# ST_LINK_V2-1.net
KiCad netlist of a schematic drawn in Altium Designer
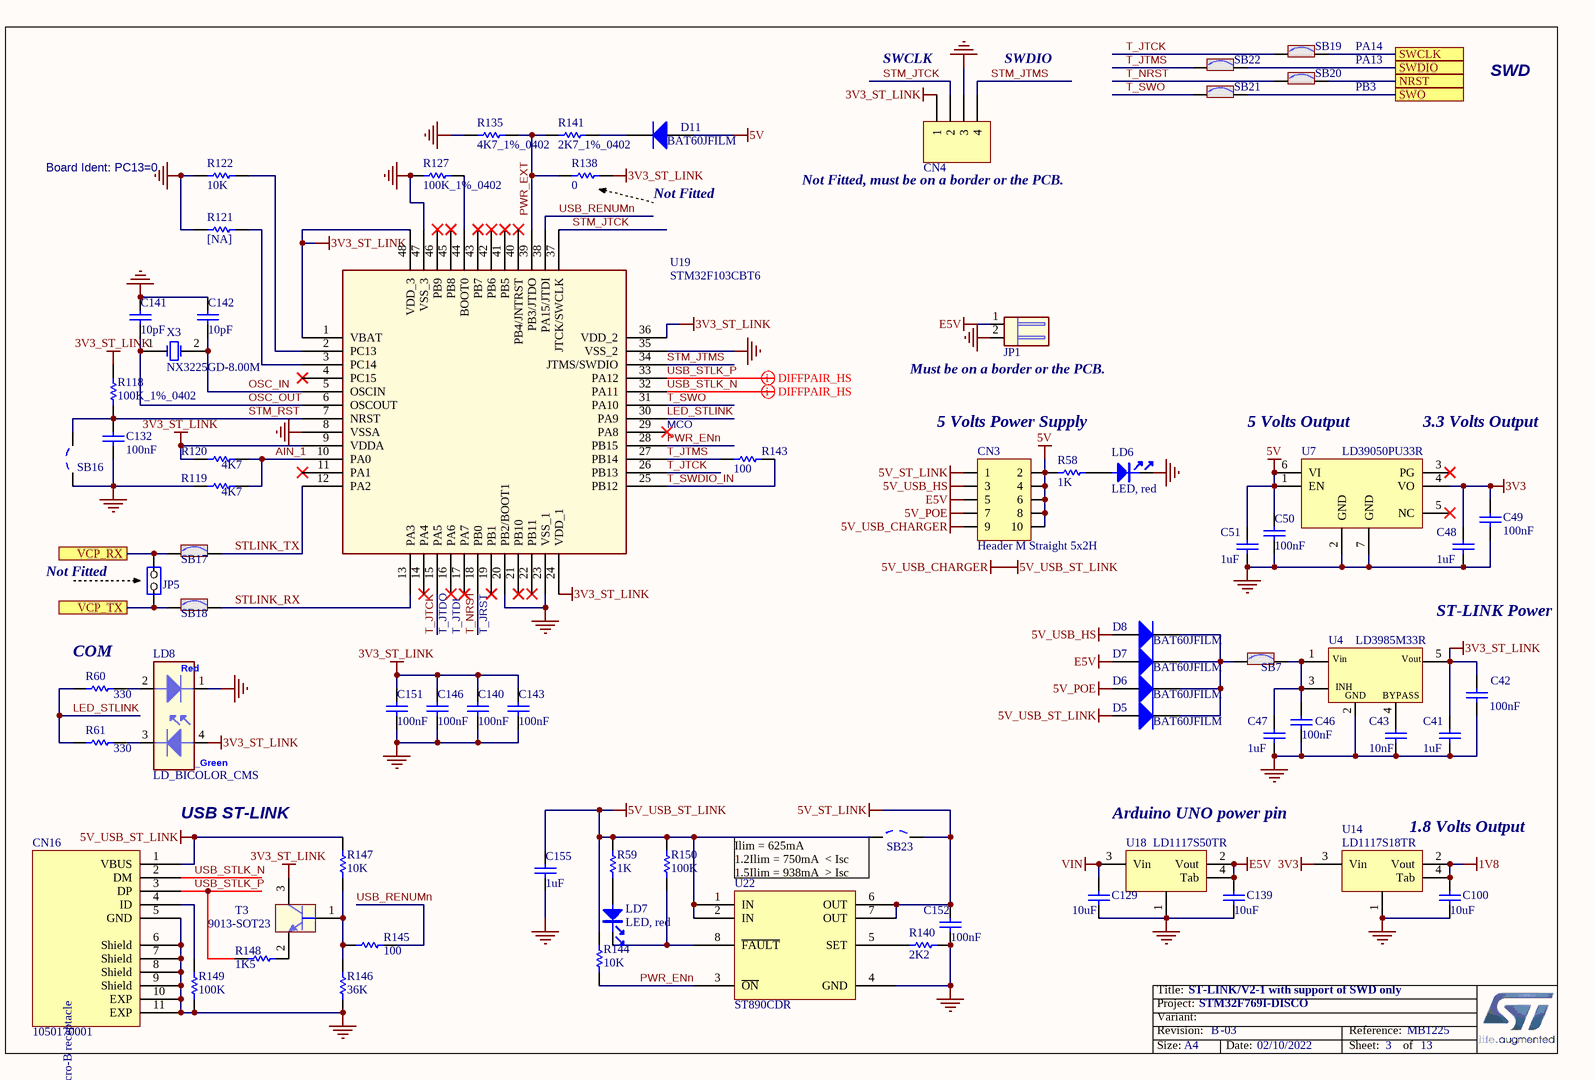
[diagram p0: ST_LINK_V2-1.SCHDOC]

(export (version "E")
  (design (tool "Eeschema 10.0.6"))
  (components
    (comp (ref "C41")
      (value "1uF")
      (footprint "0603C")
      (description "Capacitor,1uF,16V,X5R,10%,0603,YAGEO")
      (libsource (lib "MCD_TOOLS") (part "Cap_1uF_X5R_10%_0603"))
    )
    (comp (ref "C42")
      (value "100nF")
      (footprint "0402C")
      (description "Capacitor,100nF,16V,X7R,10%,0402,YAGEO")
      (libsource (lib "MCD_TOOLS") (part "Cap_100nF_X7R_10%_0402"))
    )
    (comp (ref "C43")
      (value "10nF")
      (footprint "0603C")
      (description "Capacitor,10nF,50V,X7R,10%,0603,YAGEO")
      (libsource (lib "MCD_TOOLS") (part "Cap_10nF_X7R_10%_0603"))
    )
    (comp (ref "C46")
      (value "100nF")
      (footprint "0402C")
      (description "Capacitor,100nF,16V,X7R,10%,0402,YAGEO")
      (libsource (lib "MCD_TOOLS") (part "Cap_100nF_X7R_10%_0402"))
    )
    (comp (ref "C47")
      (value "1uF")
      (footprint "0603C")
      (description "Capacitor,1uF,16V,X5R,10%,0603,YAGEO")
      (libsource (lib "MCD_TOOLS") (part "Cap_1uF_X5R_10%_0603"))
    )
    (comp (ref "C48")
      (value "1uF")
      (footprint "0603C")
      (description "Capacitor,1uF,16V,X5R,10%,0603,YAGEO")
      (libsource (lib "MCD_TOOLS") (part "Cap_1uF_X5R_10%_0603"))
    )
    (comp (ref "C49")
      (value "100nF")
      (footprint "0402C")
      (description "Capacitor,100nF,16V,X7R,10%,0402,YAGEO")
      (libsource (lib "MCD_TOOLS") (part "Cap_100nF_X7R_10%_0402"))
    )
    (comp (ref "C50")
      (value "100nF")
      (footprint "0402C")
      (description "Capacitor,100nF,16V,X7R,10%,0402,YAGEO")
      (libsource (lib "MCD_TOOLS") (part "Cap_100nF_X7R_10%_0402"))
    )
    (comp (ref "C51")
      (value "1uF")
      (footprint "0603C")
      (description "Capacitor,1uF,16V,X5R,10%,0603,YAGEO")
      (libsource (lib "MCD_TOOLS") (part "Cap_1uF_X5R_10%_0603"))
    )
    (comp (ref "C100")
      (value "10uF")
      (footprint "0603C")
      (description "Capacitor,10uF,6.3V,X5R,10%,0603,YAGEO")
      (libsource (lib "MCD_TOOLS") (part "Cap_10uF_X5R_10%_0603"))
    )
    (comp (ref "C129")
      (value "10uF")
      (footprint "0805C")
      (description "Capacitor,10uF,25V,X5R,10%,0805,YAGEO")
      (libsource (lib "MCD_TOOLS") (part "Cap_10uF_X5R_10%_0805"))
    )
    (comp (ref "C132")
      (value "100nF")
      (footprint "0402C")
      (description "Capacitor,100nF,16V,X7R,10%,0402,YAGEO")
      (libsource (lib "MCD_TOOLS") (part "Cap_100nF_X7R_10%_0402"))
    )
    (comp (ref "C139")
      (value "10uF")
      (footprint "0805C")
      (description "Capacitor,10uF,25V,X5R,10%,0805,YAGEO")
      (libsource (lib "MCD_TOOLS") (part "Cap_10uF_X5R_10%_0805"))
    )
    (comp (ref "C140")
      (value "100nF")
      (footprint "0402C")
      (description "Capacitor,100nF,16V,X7R,10%,0402,YAGEO")
      (libsource (lib "MCD_TOOLS") (part "Cap_100nF_X7R_10%_0402"))
    )
    (comp (ref "C141")
      (value "10pF")
      (footprint "0402C")
      (description "Capacitor,10pF,50V,NPO,5%,0402,YAGEO")
      (libsource (lib "MCD_TOOLS") (part "Cap_10pF_NPO_5%_0402"))
    )
    (comp (ref "C142")
      (value "10pF")
      (footprint "0402C")
      (description "Capacitor,10pF,50V,NPO,5%,0402,YAGEO")
      (libsource (lib "MCD_TOOLS") (part "Cap_10pF_NPO_5%_0402"))
    )
    (comp (ref "C143")
      (value "100nF")
      (footprint "0402C")
      (description "Capacitor,100nF,16V,X7R,10%,0402,YAGEO")
      (libsource (lib "MCD_TOOLS") (part "Cap_100nF_X7R_10%_0402"))
    )
    (comp (ref "C146")
      (value "100nF")
      (footprint "0402C")
      (description "Capacitor,100nF,16V,X7R,10%,0402,YAGEO")
      (libsource (lib "MCD_TOOLS") (part "Cap_100nF_X7R_10%_0402"))
    )
    (comp (ref "C151")
      (value "100nF")
      (footprint "0402C")
      (description "Capacitor,100nF,16V,X7R,10%,0402,YAGEO")
      (libsource (lib "MCD_TOOLS") (part "Cap_100nF_X7R_10%_0402"))
    )
    (comp (ref "C152")
      (value "100nF")
      (footprint "0402C")
      (description "Capacitor,100nF,16V,X7R,10%,0402,YAGEO")
      (libsource (lib "MCD_TOOLS") (part "Cap_100nF_X7R_10%_0402"))
    )
    (comp (ref "C155")
      (value "1uF")
      (footprint "0603C")
      (description "Capacitor,1uF,16V,X5R,10%,0603,YAGEO")
      (libsource (lib "MCD_TOOLS_CAPACITOR") (part "Cap_1uF_X5R_10%_0603"))
    )
    (comp (ref "CN3")
      (value "Header M Straight 5x2H")
      (footprint "HDR_2X5_2R54")
      (description "Header Male, 5-Pin, Dual row, Straight, AMD")
      (libsource (lib "MCD_TOOLS_CONNECTOR") (part "Header 5X2M"))
    )
    (comp (ref "CN4")
      (value "Header 4")
      (footprint "HDR_1X4_2R54")
      (description "Header, 4-Pin")
      (fields (field (name "PUBLISHER") "Altium Limited"))
      (libsource (lib "MCD_TOOLS_CONNECTOR") (part "Header 4"))
    )
    (comp (ref "CN16")
      (value "1050170001")
      (footprint "MICRO_USB_B_105017")
      (description "USB-MICRO-B, 1050170001, SMT, MOLEX")
      (libsource (lib "MCD_TOOLS_CONNECTOR") (part "1050170001"))
    )
    (comp (ref "D5")
      (value "BAT60JFILM")
      (footprint "SOD-323")
      (libsource (lib "MCD_TOOLS_MISCELLANEOUS") (part "BAT60JFILM"))
    )
    (comp (ref "D6")
      (value "BAT60JFILM")
      (footprint "SOD-323")
      (libsource (lib "MCD_TOOLS_MISCELLANEOUS") (part "BAT60JFILM"))
    )
    (comp (ref "D7")
      (value "BAT60JFILM")
      (footprint "SOD-323")
      (libsource (lib "MCD_TOOLS_MISCELLANEOUS") (part "BAT60JFILM"))
    )
    (comp (ref "D8")
      (value "BAT60JFILM")
      (footprint "SOD-323")
      (libsource (lib "MCD_TOOLS_MISCELLANEOUS") (part "BAT60JFILM"))
    )
    (comp (ref "D11")
      (value "BAT60JFILM")
      (footprint "SOD-323")
      (libsource (lib "MCD_TOOLS_MISCELLANEOUS") (part "BAT60JFILM"))
    )
    (comp (ref "JP1")
      (value "WF25402-06421")
      (footprint "HDR_1X2_2R54_RA_11R35")
      (description "Header, 2-Pins, Single row, Right Angle, 2.54 mm pitch, DIP")
      (libsource (lib "MCD_TOOLS_CONNECTOR") (part "JP2_RA"))
    )
    (comp (ref "JP5") (value "JP2") (footprint "SIP2") (libsource (lib "MCD_TOOLS_CONNECTOR") (part "JP2")))
    (comp (ref "LD6")
      (value "LED, red")
      (footprint "0603D")
      (description "LED, red, 0603")
      (libsource (lib "MCD_TOOLS") (part "LED_red"))
    )
    (comp (ref "LD7")
      (value "LED, red")
      (footprint "0603D")
      (description "LED, red, 0603")
      (libsource (lib "MCD_TOOLS") (part "LED_red"))
    )
    (comp (ref "LD8")
      (value "LD_BICOLOR_CMS")
      (footprint "LED2_3528")
      (description "Bicolor Led")
      (libsource (lib "MCD_TOOLS_MISCELLANEOUS") (part "LD_BICOLOR_CMS"))
    )
    (comp (ref "R58")
      (value "1K")
      (footprint "0402R")
      (description "Resistor,1K,0402,1%,YAGEO")
      (libsource (lib "MCD_TOOLS") (part "Res_1K_1%_0402"))
    )
    (comp (ref "R59")
      (value "1K")
      (footprint "0402R")
      (description "Resistor,1K,0402,1%,YAGEO")
      (libsource (lib "MCD_TOOLS") (part "Res_1K_1%_0402"))
    )
    (comp (ref "R60")
      (value "330")
      (footprint "0402R")
      (description "Resistor,330,0402,1%,YAGEO")
      (libsource (lib "MCD_TOOLS") (part "Res_330_1%_0402"))
    )
    (comp (ref "R61")
      (value "330")
      (footprint "0402R")
      (description "Resistor,330,0402,1%,YAGEO")
      (libsource (lib "MCD_TOOLS") (part "Res_330_1%_0402"))
    )
    (comp (ref "R118")
      (value "100K_1%_0402")
      (footprint "0402R")
      (description "Resistor,100K,0402,1%,YAGEO")
      (libsource (lib "MCD_TOOLS_RESISTOR") (part "Res_100K_1%_0402"))
    )
    (comp (ref "R119")
      (value "4K7")
      (footprint "0402R")
      (description "Resistor,4K7,0402,1%,YAGEO")
      (libsource (lib "MCD_TOOLS_RESISTOR") (part "Res_4K7_1%_0402"))
    )
    (comp (ref "R120")
      (value "4K7")
      (footprint "0402R")
      (description "Resistor,4K7,0402,1%,YAGEO")
      (libsource (lib "MCD_TOOLS_RESISTOR") (part "Res_4K7_1%_0402"))
    )
    (comp (ref "R121")
      (value "[NA]")
      (footprint "0402R")
      (description "Resistor,[NA],0402")
      (libsource (lib "MCD_TOOLS") (part "Res_NA_0402"))
    )
    (comp (ref "R122")
      (value "10K")
      (footprint "0402R")
      (description "Resistor,10K,0402,1%,YAGEO")
      (libsource (lib "MCD_TOOLS") (part "Res_10K_1%_0402"))
    )
    (comp (ref "R127")
      (value "100K_1%_0402")
      (footprint "0402R")
      (description "Resistor,100K,0402,1%,YAGEO")
      (libsource (lib "MCD_TOOLS_RESISTOR") (part "Res_100K_1%_0402"))
    )
    (comp (ref "R135")
      (value "4K7_1%_0402")
      (footprint "0402R")
      (description "Resistor,4K7,0402,1%,YAGEO")
      (libsource (lib "MCD_TOOLS_RESISTOR") (part "Res_4K7_1%_0402"))
    )
    (comp (ref "R138")
      (value "0")
      (footprint "0402R")
      (description "Resistor,0,0402,5%,YAGEO")
      (libsource (lib "MCD_TOOLS") (part "Res_0_5%_0402"))
    )
    (comp (ref "R140")
      (value "2K2")
      (footprint "0402R")
      (description "Resistor,2K2,0402,1%,YAGEO")
      (libsource (lib "MCD_TOOLS_RESISTOR") (part "Res_2K2_1%_0402"))
    )
    (comp (ref "R141")
      (value "2K7_1%_0402")
      (footprint "0402R")
      (description "Resistor,2K7,0402,1%,YAGEO")
      (libsource (lib "MCD_TOOLS_RESISTOR") (part "Res_2K7_1%_0402"))
    )
    (comp (ref "R143")
      (value "100")
      (footprint "0402R")
      (description "Resistor,100,0402,1%,YAGEO")
      (libsource (lib "MCD_TOOLS") (part "Res_100_1%_0402"))
    )
    (comp (ref "R144")
      (value "10K")
      (footprint "0402R")
      (description "Resistor,10K,0402,1%,YAGEO")
      (libsource (lib "MCD_TOOLS") (part "Res_10K_1%_0402"))
    )
    (comp (ref "R145")
      (value "100")
      (footprint "0402R")
      (description "Resistor,100,0402,1%,YAGEO")
      (libsource (lib "MCD_TOOLS") (part "Res_100_1%_0402"))
    )
    (comp (ref "R146")
      (value "36K")
      (footprint "0402R")
      (description "Resistor,36K,0402,1%,YAGEO")
      (libsource (lib "MCD_TOOLS") (part "Res_36K_1%_0402"))
    )
    (comp (ref "R147")
      (value "10K")
      (footprint "0402R")
      (description "Resistor,10K,0402,1%,YAGEO")
      (libsource (lib "MCD_TOOLS") (part "Res_10K_1%_0402"))
    )
    (comp (ref "R148")
      (value "1K5")
      (footprint "0402R")
      (description "Resistor,1K5,0402,1%,YAGEO")
      (libsource (lib "MCD_TOOLS") (part "Res_1K5_1%_0402"))
    )
    (comp (ref "R149")
      (value "100K")
      (footprint "0402R")
      (description "Resistor,100K,0402,1%,YAGEO")
      (libsource (lib "MCD_TOOLS_RESISTOR") (part "Res_100K_1%_0402"))
    )
    (comp (ref "R150")
      (value "100K")
      (footprint "0402R")
      (description "Resistor,100K,0402,1%,YAGEO")
      (libsource (lib "MCD_TOOLS_RESISTOR") (part "Res_100K_1%_0402"))
    )
    (comp (ref "SB7")
      (value "Solder Bridge ON")
      (footprint "JP2_SMD")
      (libsource (lib "MCD_TOOLS") (part "SB_ON"))
    )
    (comp (ref "SB16")
      (value "Solder Bridge OFF")
      (footprint "JP2_SMD")
      (libsource (lib "MCD_TOOLS") (part "SB_OFF"))
    )
    (comp (ref "SB17")
      (value "Solder Bridge ON")
      (footprint "JP2_SMD")
      (libsource (lib "MCD_TOOLS") (part "SB_ON"))
    )
    (comp (ref "SB18")
      (value "Solder Bridge ON")
      (footprint "JP2_SMD")
      (libsource (lib "MCD_TOOLS") (part "SB_ON"))
    )
    (comp (ref "SB19")
      (value "Solder Bridge ON")
      (footprint "JP2_SMD")
      (libsource (lib "MCD_TOOLS") (part "SB_ON"))
    )
    (comp (ref "SB20")
      (value "Solder Bridge ON")
      (footprint "JP2_SMD")
      (libsource (lib "MCD_TOOLS") (part "SB_ON"))
    )
    (comp (ref "SB21")
      (value "Solder Bridge ON")
      (footprint "JP2_SMD")
      (libsource (lib "MCD_TOOLS") (part "SB_ON"))
    )
    (comp (ref "SB22")
      (value "Solder Bridge ON")
      (footprint "JP2_SMD")
      (libsource (lib "MCD_TOOLS") (part "SB_ON"))
    )
    (comp (ref "SB23")
      (value "Solder Bridge OFF")
      (footprint "JP2_SMD")
      (libsource (lib "MCD_TOOLS") (part "SB_OFF"))
    )
    (comp (ref "T3")
      (value "9013-SOT23")
      (footprint "SOT-23")
      (description "NPN Bipolar Transistor")
      (libsource (lib "MCD_TOOLS_MISCELLANEOUS") (part "9013-SOT23"))
    )
    (comp (ref "U4")
      (value "LD3985M33R")
      (footprint "SOT-23-5L")
      (description "Ultra low drop-low noise BiCMOS voltage, regulators low ESR capacitors compatible")
      (libsource (lib "MCD_TOOLS_MISCELLANEOUS") (part "LD3985M33R"))
    )
    (comp (ref "U7")
      (value "LD39050PU33R")
      (footprint "DFN6_0R95_3X3")
      (description "Ultra low drop-low , 500 mA low quiescent current")
      (libsource (lib "MCD_TOOLS_MISCELLANEOUS") (part "LD39050P"))
    )
    (comp (ref "U14")
      (value "LD1117S18TR")
      (footprint "SOT-223")
      (description "LOW DROP FIXED AND ADJUSTABLE POSITIVE VOLTAGE REGULATORS (1.8 Volts)")
      (libsource (lib "MCD_TOOLS") (part "LD1117S18TR"))
    )
    (comp (ref "U18")
      (value "LD1117S50TR")
      (footprint "SOT-223")
      (description "IC REG LDO 5V 0.8A SOT223")
      (libsource (lib "MCD_TOOLS") (part "LD1117S50TR"))
    )
    (comp (ref "U19")
      (value "STM32F103CBT6")
      (footprint "LQFP48_0R5_9X9")
      (description "Medium-density performance line ARM-based 32-bit MCU with 128KB Flash")
      (libsource (lib "MCD_TOOLS_MCU") (part "STM32F103CBT6"))
    )
    (comp (ref "U22")
      (value "ST890CDR")
      (footprint "SOIC8_1R27_4R9X6")
      (description "1.2 A current limited high-side power switch with thermal shutdown")
      (libsource (lib "MCD_TOOLS_MISCELLANEOUS") (part "ST890CDR"))
    )
    (comp (ref "X3")
      (value "NX3225GD-8.00M")
      (footprint "XTAL_2SM_3R2X2R5_H1")
      (description "Crystal 8Mhz, 8pF, -+50PPM, SMD")
      (libsource (lib "MCD_TOOLS_MISCELLANEOUS") (part "XTAL_8M_NX3225GD"))
    )
  )
  (nets
    (net (code "1") (name "/AIN_1") (class "Default")
      (node (ref "R119") (pin "2") (pinfunction "2_2") (pintype "passive"))
      (node (ref "R120") (pin "2") (pinfunction "2_2") (pintype "passive"))
      (node (ref "U19") (pin "10") (pinfunction "PA0_10") (pintype "passive"))
    )
    (net (code "2") (name "/LED_STLINK") (class "Default")
      (node (ref "R60") (pin "1") (pinfunction "1_1") (pintype "passive"))
      (node (ref "R61") (pin "1") (pinfunction "1_1") (pintype "passive"))
      (node (ref "U19") (pin "30") (pinfunction "PA9_30") (pintype "passive"))
    )
    (net (code "3") (name "/NRST") (class "Default")
      (node (ref "SB20") (pin "2") (pinfunction "2_2") (pintype "passive"))
    )
    (net (code "4") (name "/OSC_IN") (class "Default")
      (node (ref "C142") (pin "2") (pinfunction "2_2") (pintype "passive"))
      (node (ref "U19") (pin "5") (pinfunction "OSCIN_5") (pintype "passive"))
      (node (ref "X3") (pin "2") (pinfunction "OSC2_2") (pintype "passive"))
    )
    (net (code "5") (name "/OSC_OUT") (class "Default")
      (node (ref "C141") (pin "2") (pinfunction "2_2") (pintype "passive"))
      (node (ref "U19") (pin "6") (pinfunction "OSCOUT_6") (pintype "passive"))
      (node (ref "X3") (pin "1") (pinfunction "OSC1_1") (pintype "passive"))
    )
    (net (code "6") (name "/PWR_ENn") (class "Default")
      (node (ref "R144") (pin "1") (pinfunction "1_1") (pintype "passive"))
      (node (ref "U19") (pin "28") (pinfunction "PB15_28") (pintype "passive"))
      (node (ref "U22") (pin "3") (pinfunction "~{ON}_3") (pintype "passive"))
    )
    (net (code "7") (name "/PWR_EXT") (class "Default")
      (node (ref "R135") (pin "2") (pinfunction "2_2") (pintype "passive"))
      (node (ref "R138") (pin "1") (pinfunction "1_1") (pintype "passive"))
      (node (ref "R141") (pin "1") (pinfunction "1_1") (pintype "passive"))
      (node (ref "U19") (pin "39") (pinfunction "PB3/JTDO_39") (pintype "passive"))
    )
    (net (code "8") (name "/STLINK_RX") (class "Default")
      (node (ref "SB18") (pin "2") (pinfunction "2_2") (pintype "passive"))
      (node (ref "U19") (pin "13") (pinfunction "PA3_13") (pintype "passive"))
    )
    (net (code "9") (name "/STLINK_TX") (class "Default")
      (node (ref "SB17") (pin "2") (pinfunction "2_2") (pintype "passive"))
      (node (ref "U19") (pin "12") (pinfunction "PA2_12") (pintype "passive"))
    )
    (net (code "10") (name "/STM_JTCK") (class "Default")
      (node (ref "CN4") (pin "2") (pinfunction "2_2") (pintype "passive"))
      (node (ref "U19") (pin "37") (pinfunction "JTCK/SWCLK_37") (pintype "passive"))
    )
    (net (code "11") (name "/STM_JTMS") (class "Default")
      (node (ref "CN4") (pin "4") (pinfunction "4_4") (pintype "passive"))
      (node (ref "U19") (pin "34") (pinfunction "JTMS/SWDIO_34") (pintype "passive"))
    )
    (net (code "12") (name "/STM_RST") (class "Default")
      (node (ref "C132") (pin "2") (pinfunction "2_2") (pintype "passive"))
      (node (ref "R118") (pin "1") (pinfunction "1_1") (pintype "passive"))
      (node (ref "SB16") (pin "2") (pinfunction "2_2") (pintype "passive"))
      (node (ref "U19") (pin "7") (pinfunction "NRST_7") (pintype "passive"))
    )
    (net (code "13") (name "/SWCLK") (class "Default")
      (node (ref "SB19") (pin "2") (pinfunction "2_2") (pintype "passive"))
    )
    (net (code "14") (name "/SWDIO") (class "Default")
      (node (ref "SB22") (pin "2") (pinfunction "2_2") (pintype "passive"))
    )
    (net (code "15") (name "/SWO") (class "Default")
      (node (ref "SB21") (pin "2") (pinfunction "2_2") (pintype "passive"))
    )
    (net (code "16") (name "/T_JTCK") (class "Default")
      (node (ref "SB19") (pin "1") (pinfunction "1_1") (pintype "passive"))
      (node (ref "U19") (pin "15") (pinfunction "PA5_15") (pintype "passive"))
      (node (ref "U19") (pin "26") (pinfunction "PB13_26") (pintype "passive"))
    )
    (net (code "17") (name "/T_JTMS") (class "Default")
      (node (ref "R143") (pin "1") (pinfunction "1_1") (pintype "passive"))
      (node (ref "SB22") (pin "1") (pinfunction "1_1") (pintype "passive"))
      (node (ref "U19") (pin "27") (pinfunction "PB14_27") (pintype "passive"))
    )
    (net (code "18") (name "/T_NRST") (class "Default")
      (node (ref "SB20") (pin "1") (pinfunction "1_1") (pintype "passive"))
      (node (ref "U19") (pin "18") (pinfunction "PB0_18") (pintype "passive"))
    )
    (net (code "19") (name "/T_SWDIO_IN") (class "Default")
      (node (ref "R143") (pin "2") (pinfunction "2_2") (pintype "passive"))
      (node (ref "U19") (pin "25") (pinfunction "PB12_25") (pintype "passive"))
    )
    (net (code "20") (name "/T_SWO") (class "Default")
      (node (ref "SB21") (pin "1") (pinfunction "1_1") (pintype "passive"))
      (node (ref "U19") (pin "31") (pinfunction "PA10_31") (pintype "passive"))
    )
    (net (code "21") (name "/USB_RENUMn") (class "Default")
      (node (ref "R145") (pin "2") (pinfunction "2_2") (pintype "passive"))
      (node (ref "U19") (pin "38") (pinfunction "PA15/JTDI_38") (pintype "passive"))
    )
    (net (code "22") (name "/USB_STLK_N") (class "Default")
      (node (ref "CN16") (pin "2") (pinfunction "DM_2") (pintype "passive"))
      (node (ref "U19") (pin "32") (pinfunction "PA11_32") (pintype "passive"))
    )
    (net (code "23") (name "/USB_STLK_P") (class "Default")
      (node (ref "CN16") (pin "3") (pinfunction "DP_3") (pintype "passive"))
      (node (ref "R148") (pin "1") (pinfunction "1_1") (pintype "passive"))
      (node (ref "U19") (pin "33") (pinfunction "PA12_33") (pintype "passive"))
    )
    (net (code "24") (name "/VCP_RX") (class "Default")
      (node (ref "JP5") (pin "2") (pinfunction "NO_2") (pintype "passive"))
      (node (ref "SB17") (pin "1") (pinfunction "1_1") (pintype "passive"))
    )
    (net (code "25") (name "/VCP_TX") (class "Default")
      (node (ref "JP5") (pin "1") (pinfunction "COMMON_1") (pintype "passive"))
      (node (ref "SB18") (pin "1") (pinfunction "1_1") (pintype "passive"))
    )
    (net (code "26") (name "1V8") (class "Default")
      (node (ref "C100") (pin "2") (pinfunction "2_2") (pintype "passive"))
      (node (ref "U14") (pin "2") (pinfunction "Vout_2") (pintype "passive"))
      (node (ref "U14") (pin "4") (pinfunction "Tab_4") (pintype "passive"))
    )
    (net (code "27") (name "3V3") (class "Default")
      (node (ref "C48") (pin "2") (pinfunction "2_2") (pintype "passive"))
      (node (ref "C49") (pin "2") (pinfunction "2_2") (pintype "passive"))
      (node (ref "U14") (pin "3") (pinfunction "Vin_3") (pintype "passive"))
      (node (ref "U7") (pin "4") (pinfunction "VO_4") (pintype "passive"))
    )
    (net (code "28") (name "3V3_ST_LINK") (class "Default")
      (node (ref "C140") (pin "1") (pinfunction "1_1") (pintype "passive"))
      (node (ref "C143") (pin "2") (pinfunction "2_2") (pintype "passive"))
      (node (ref "C146") (pin "2") (pinfunction "2_2") (pintype "passive"))
      (node (ref "C151") (pin "2") (pinfunction "2_2") (pintype "passive"))
      (node (ref "C41") (pin "1") (pinfunction "1_1") (pintype "passive"))
      (node (ref "C42") (pin "2") (pinfunction "2_2") (pintype "passive"))
      (node (ref "CN4") (pin "1") (pinfunction "1_1") (pintype "passive"))
      (node (ref "LD8") (pin "4") (pinfunction "4_4") (pintype "passive"))
      (node (ref "R118") (pin "2") (pinfunction "2_2") (pintype "passive"))
      (node (ref "R120") (pin "1") (pinfunction "1_1") (pintype "passive"))
      (node (ref "R138") (pin "2") (pinfunction "2_2") (pintype "passive"))
      (node (ref "T3") (pin "3") (pinfunction "C_3") (pintype "passive"))
      (node (ref "U19") (pin "1") (pinfunction "VBAT_1") (pintype "passive"))
      (node (ref "U19") (pin "24") (pinfunction "VDD_1_24") (pintype "passive"))
      (node (ref "U19") (pin "36") (pinfunction "VDD_2_36") (pintype "passive"))
      (node (ref "U19") (pin "48") (pinfunction "VDD_3_48") (pintype "passive"))
      (node (ref "U19") (pin "9") (pinfunction "VDDA_9") (pintype "passive"))
      (node (ref "U4") (pin "5") (pinfunction "Vout_5") (pintype "passive"))
    )
    (net (code "29") (name "5V") (class "Default")
      (node (ref "C50") (pin "2") (pinfunction "2_2") (pintype "passive"))
      (node (ref "C51") (pin "2") (pinfunction "2_2") (pintype "passive"))
      (node (ref "CN3") (pin "10") (pinfunction "10_10") (pintype "passive"))
      (node (ref "CN3") (pin "2") (pinfunction "2_2") (pintype "passive"))
      (node (ref "CN3") (pin "4") (pinfunction "4_4") (pintype "passive"))
      (node (ref "CN3") (pin "6") (pinfunction "6_6") (pintype "passive"))
      (node (ref "CN3") (pin "8") (pinfunction "8_8") (pintype "passive"))
      (node (ref "D11") (pin "1") (pinfunction "A_1") (pintype "passive"))
      (node (ref "R58") (pin "1") (pinfunction "1_1") (pintype "passive"))
      (node (ref "U7") (pin "1") (pinfunction "EN_1") (pintype "passive"))
      (node (ref "U7") (pin "6") (pinfunction "VI_6") (pintype "passive"))
    )
    (net (code "30") (name "5V_POE") (class "Default")
      (node (ref "CN3") (pin "7") (pinfunction "7_7") (pintype "passive"))
      (node (ref "D6") (pin "1") (pinfunction "A_1") (pintype "passive"))
    )
    (net (code "31") (name "5V_ST_LINK") (class "Default")
      (node (ref "C152") (pin "2") (pinfunction "2_2") (pintype "passive"))
      (node (ref "CN3") (pin "1") (pinfunction "1_1") (pintype "passive"))
      (node (ref "SB23") (pin "2") (pinfunction "2_2") (pintype "passive"))
      (node (ref "U22") (pin "6") (pinfunction "OUT_6") (pintype "passive"))
      (node (ref "U22") (pin "7") (pinfunction "OUT_7") (pintype "passive"))
    )
    (net (code "32") (name "5V_USB_CHARGER") (class "Default")
      (node (ref "C155") (pin "2") (pinfunction "2_2") (pintype "passive"))
      (node (ref "CN16") (pin "1") (pinfunction "VBUS_1") (pintype "passive"))
      (node (ref "CN3") (pin "9") (pinfunction "9_9") (pintype "passive"))
      (node (ref "D5") (pin "1") (pinfunction "A_1") (pintype "passive"))
      (node (ref "R144") (pin "2") (pinfunction "2_2") (pintype "passive"))
      (node (ref "R147") (pin "2") (pinfunction "2_2") (pintype "passive"))
      (node (ref "R150") (pin "2") (pinfunction "2_2") (pintype "passive"))
      (node (ref "R59") (pin "2") (pinfunction "2_2") (pintype "passive"))
      (node (ref "SB23") (pin "1") (pinfunction "1_1") (pintype "passive"))
      (node (ref "U22") (pin "1") (pinfunction "IN_1") (pintype "passive"))
      (node (ref "U22") (pin "2") (pinfunction "IN_2") (pintype "passive"))
    )
    (net (code "33") (name "5V_USB_HS") (class "Default")
      (node (ref "CN3") (pin "3") (pinfunction "3_3") (pintype "passive"))
      (node (ref "D8") (pin "1") (pinfunction "A_1") (pintype "passive"))
    )
    (net (code "34") (name "E5V") (class "Default")
      (node (ref "C139") (pin "2") (pinfunction "2_2") (pintype "passive"))
      (node (ref "CN3") (pin "5") (pinfunction "5_5") (pintype "passive"))
      (node (ref "D7") (pin "1") (pinfunction "A_1") (pintype "passive"))
      (node (ref "JP1") (pin "1") (pinfunction "1_1") (pintype "passive"))
      (node (ref "U18") (pin "2") (pinfunction "Vout_2") (pintype "passive"))
      (node (ref "U18") (pin "4") (pinfunction "Tab_4") (pintype "passive"))
    )
    (net (code "35") (name "GND") (class "Default")
      (node (ref "C100") (pin "1") (pinfunction "1_1") (pintype "passive"))
      (node (ref "C129") (pin "1") (pinfunction "1_1") (pintype "passive"))
      (node (ref "C132") (pin "1") (pinfunction "1_1") (pintype "passive"))
      (node (ref "C139") (pin "1") (pinfunction "1_1") (pintype "passive"))
      (node (ref "C140") (pin "2") (pinfunction "2_2") (pintype "passive"))
      (node (ref "C141") (pin "1") (pinfunction "1_1") (pintype "passive"))
      (node (ref "C142") (pin "1") (pinfunction "1_1") (pintype "passive"))
      (node (ref "C143") (pin "1") (pinfunction "1_1") (pintype "passive"))
      (node (ref "C146") (pin "1") (pinfunction "1_1") (pintype "passive"))
      (node (ref "C151") (pin "1") (pinfunction "1_1") (pintype "passive"))
      (node (ref "C152") (pin "1") (pinfunction "1_1") (pintype "passive"))
      (node (ref "C155") (pin "1") (pinfunction "1_1") (pintype "passive"))
      (node (ref "C41") (pin "2") (pinfunction "2_2") (pintype "passive"))
      (node (ref "C42") (pin "1") (pinfunction "1_1") (pintype "passive"))
      (node (ref "C43") (pin "1") (pinfunction "1_1") (pintype "passive"))
      (node (ref "C46") (pin "1") (pinfunction "1_1") (pintype "passive"))
      (node (ref "C47") (pin "1") (pinfunction "1_1") (pintype "passive"))
      (node (ref "C48") (pin "1") (pinfunction "1_1") (pintype "passive"))
      (node (ref "C49") (pin "1") (pinfunction "1_1") (pintype "passive"))
      (node (ref "C50") (pin "1") (pinfunction "1_1") (pintype "passive"))
      (node (ref "C51") (pin "1") (pinfunction "1_1") (pintype "passive"))
      (node (ref "CN16") (pin "10") (pinfunction "EXP_10") (pintype "passive"))
      (node (ref "CN16") (pin "11") (pinfunction "EXP_11") (pintype "passive"))
      (node (ref "CN16") (pin "5") (pinfunction "GND_5") (pintype "passive"))
      (node (ref "CN16") (pin "6") (pinfunction "Shield_6") (pintype "passive"))
      (node (ref "CN16") (pin "7") (pinfunction "Shield_7") (pintype "passive"))
      (node (ref "CN16") (pin "8") (pinfunction "Shield_8") (pintype "passive"))
      (node (ref "CN16") (pin "9") (pinfunction "Shield_9") (pintype "passive"))
      (node (ref "CN4") (pin "3") (pinfunction "3_3") (pintype "passive"))
      (node (ref "JP1") (pin "2") (pinfunction "2_2") (pintype "passive"))
      (node (ref "LD6") (pin "2") (pintype "passive"))
      (node (ref "LD8") (pin "1") (pinfunction "1_1") (pintype "passive"))
      (node (ref "R119") (pin "1") (pinfunction "1_1") (pintype "passive"))
      (node (ref "R121") (pin "1") (pinfunction "1_1") (pintype "passive"))
      (node (ref "R122") (pin "1") (pinfunction "1_1") (pintype "passive"))
      (node (ref "R127") (pin "1") (pinfunction "1_1") (pintype "passive"))
      (node (ref "R135") (pin "1") (pinfunction "1_1") (pintype "passive"))
      (node (ref "R140") (pin "2") (pinfunction "2_2") (pintype "passive"))
      (node (ref "R146") (pin "1") (pinfunction "1_1") (pintype "passive"))
      (node (ref "R149") (pin "1") (pinfunction "1_1") (pintype "passive"))
      (node (ref "SB16") (pin "1") (pinfunction "1_1") (pintype "passive"))
      (node (ref "U14") (pin "1") (pintype "passive"))
      (node (ref "U18") (pin "1") (pintype "passive"))
      (node (ref "U19") (pin "20") (pinfunction "PB2/BOOT1_20") (pintype "passive"))
      (node (ref "U19") (pin "23") (pinfunction "VSS_1_23") (pintype "passive"))
      (node (ref "U19") (pin "35") (pinfunction "VSS_2_35") (pintype "passive"))
      (node (ref "U19") (pin "47") (pinfunction "VSS_3_47") (pintype "passive"))
      (node (ref "U19") (pin "8") (pinfunction "VSSA_8") (pintype "passive"))
      (node (ref "U22") (pin "4") (pinfunction "GND_4") (pintype "passive"))
      (node (ref "U4") (pin "2") (pinfunction "GND_2") (pintype "passive"))
      (node (ref "U7") (pin "2") (pinfunction "GND_2") (pintype "passive"))
      (node (ref "U7") (pin "7") (pinfunction "GND_7") (pintype "passive"))
    )
    (net (code "36") (name "Net-(CN16-ID)") (class "Default")
      (node (ref "CN16") (pin "4") (pinfunction "ID_4") (pintype "passive"))
      (node (ref "R149") (pin "2") (pinfunction "2_2") (pintype "passive"))
    )
    (net (code "37") (name "Net-(D5-K)") (class "Default")
      (node (ref "D5") (pin "2") (pinfunction "K_2") (pintype "passive"))
      (node (ref "D6") (pin "2") (pinfunction "K_2") (pintype "passive"))
      (node (ref "D7") (pin "2") (pinfunction "K_2") (pintype "passive"))
      (node (ref "D8") (pin "2") (pinfunction "K_2") (pintype "passive"))
      (node (ref "SB7") (pin "1") (pinfunction "1_1") (pintype "passive"))
    )
    (net (code "38") (name "Net-(D11-K)") (class "Default")
      (node (ref "D11") (pin "2") (pinfunction "K_2") (pintype "passive"))
      (node (ref "R141") (pin "2") (pinfunction "2_2") (pintype "passive"))
    )
    (net (code "39") (name "Net-(LD6-Pad1)") (class "Default")
      (node (ref "LD6") (pin "1") (pintype "passive"))
      (node (ref "R58") (pin "2") (pinfunction "2_2") (pintype "passive"))
    )
    (net (code "40") (name "Net-(LD7-Pad1)") (class "Default")
      (node (ref "LD7") (pin "1") (pintype "passive"))
      (node (ref "R59") (pin "1") (pinfunction "1_1") (pintype "passive"))
    )
    (net (code "41") (name "Net-(LD8-Pad2)") (class "Default")
      (node (ref "LD8") (pin "2") (pinfunction "2_2") (pintype "passive"))
      (node (ref "R60") (pin "2") (pinfunction "2_2") (pintype "passive"))
    )
    (net (code "42") (name "Net-(LD8-Pad3)") (class "Default")
      (node (ref "LD8") (pin "3") (pinfunction "3_3") (pintype "passive"))
      (node (ref "R61") (pin "2") (pinfunction "2_2") (pintype "passive"))
    )
    (net (code "43") (name "Net-(T3-B)") (class "Default")
      (node (ref "R145") (pin "1") (pinfunction "1_1") (pintype "passive"))
      (node (ref "R146") (pin "2") (pinfunction "2_2") (pintype "passive"))
      (node (ref "R147") (pin "1") (pinfunction "1_1") (pintype "passive"))
      (node (ref "T3") (pin "1") (pinfunction "B_1") (pintype "passive"))
    )
    (net (code "44") (name "Net-(T3-E)") (class "Default")
      (node (ref "R148") (pin "2") (pinfunction "2_2") (pintype "passive"))
      (node (ref "T3") (pin "2") (pinfunction "E_2") (pintype "passive"))
    )
    (net (code "45") (name "Net-(U4-BYPASS)") (class "Default")
      (node (ref "C43") (pin "2") (pinfunction "2_2") (pintype "passive"))
      (node (ref "U4") (pin "4") (pinfunction "BYPASS_4") (pintype "passive"))
    )
    (net (code "46") (name "Net-(U4-CE)") (class "Default")
      (node (ref "C46") (pin "2") (pinfunction "2_2") (pintype "passive"))
      (node (ref "C47") (pin "2") (pinfunction "2_2") (pintype "passive"))
      (node (ref "SB7") (pin "2") (pinfunction "2_2") (pintype "passive"))
      (node (ref "U4") (pin "1") (pinfunction "Vin_1") (pintype "passive"))
      (node (ref "U4") (pin "3") (pinfunction "CE_3") (pintype "passive"))
    )
    (net (code "47") (name "Net-(U19-BOOT0)") (class "Default")
      (node (ref "R127") (pin "2") (pinfunction "2_2") (pintype "passive"))
      (node (ref "U19") (pin "44") (pinfunction "BOOT0_44") (pintype "passive"))
    )
    (net (code "48") (name "Net-(U19-PC13)") (class "Default")
      (node (ref "R122") (pin "2") (pinfunction "2_2") (pintype "passive"))
      (node (ref "U19") (pin "2") (pinfunction "PC13_2") (pintype "passive"))
    )
    (net (code "49") (name "Net-(U19-PC14)") (class "Default")
      (node (ref "R121") (pin "2") (pinfunction "2_2") (pintype "passive"))
      (node (ref "U19") (pin "3") (pinfunction "PC14_3") (pintype "passive"))
    )
    (net (code "50") (name "Net-(U22-SET)") (class "Default")
      (node (ref "R140") (pin "1") (pinfunction "1_1") (pintype "passive"))
      (node (ref "U22") (pin "5") (pinfunction "SET_5") (pintype "passive"))
    )
    (net (code "51") (name "Net-(U22-~{FAULT})") (class "Default")
      (node (ref "LD7") (pin "2") (pintype "passive"))
      (node (ref "R150") (pin "1") (pinfunction "1_1") (pintype "passive"))
      (node (ref "U22") (pin "8") (pinfunction "~{FAULT}_8") (pintype "passive"))
    )
    (net (code "52") (name "VIN") (class "Default")
      (node (ref "C129") (pin "2") (pinfunction "2_2") (pintype "passive"))
      (node (ref "U18") (pin "3") (pinfunction "Vin_3") (pintype "passive"))
    )
    (net (code "53") (name "unconnected-(U7-NC-Pad5)") (class "Default")
      (node (ref "U7") (pin "5") (pinfunction "NC_5") (pintype "passive+no_connect"))
    )
    (net (code "54") (name "unconnected-(U7-PG-Pad3)") (class "Default")
      (node (ref "U7") (pin "3") (pinfunction "PG_3") (pintype "passive+no_connect"))
    )
    (net (code "55") (name "unconnected-(U19-PA1-Pad11)") (class "Default")
      (node (ref "U19") (pin "11") (pinfunction "PA1_11") (pintype "passive+no_connect"))
    )
    (net (code "56") (name "unconnected-(U19-PA4-Pad14)") (class "Default")
      (node (ref "U19") (pin "14") (pinfunction "PA4_14") (pintype "passive+no_connect"))
    )
    (net (code "57") (name "unconnected-(U19-PA6-Pad16)") (class "Default")
      (node (ref "U19") (pin "16") (pinfunction "PA6_16") (pintype "passive+no_connect"))
    )
    (net (code "58") (name "unconnected-(U19-PA7-Pad17)") (class "Default")
      (node (ref "U19") (pin "17") (pinfunction "PA7_17") (pintype "passive+no_connect"))
    )
    (net (code "59") (name "unconnected-(U19-PA8-Pad29)") (class "Default")
      (node (ref "U19") (pin "29") (pinfunction "PA8_29") (pintype "passive+no_connect"))
    )
    (net (code "60") (name "unconnected-(U19-PB1-Pad19)") (class "Default")
      (node (ref "U19") (pin "19") (pinfunction "PB1_19") (pintype "passive+no_connect"))
    )
    (net (code "61") (name "unconnected-(U19-PB4{slash}JNTRST-Pad40)") (class "Default")
      (node (ref "U19") (pin "40") (pinfunction "PB4/JNTRST_40") (pintype "passive+no_connect"))
    )
    (net (code "62") (name "unconnected-(U19-PB5-Pad41)") (class "Default")
      (node (ref "U19") (pin "41") (pinfunction "PB5_41") (pintype "passive+no_connect"))
    )
    (net (code "63") (name "unconnected-(U19-PB6-Pad42)") (class "Default")
      (node (ref "U19") (pin "42") (pinfunction "PB6_42") (pintype "passive+no_connect"))
    )
    (net (code "64") (name "unconnected-(U19-PB7-Pad43)") (class "Default")
      (node (ref "U19") (pin "43") (pinfunction "PB7_43") (pintype "passive+no_connect"))
    )
    (net (code "65") (name "unconnected-(U19-PB8-Pad45)") (class "Default")
      (node (ref "U19") (pin "45") (pinfunction "PB8_45") (pintype "passive+no_connect"))
    )
    (net (code "66") (name "unconnected-(U19-PB9-Pad46)") (class "Default")
      (node (ref "U19") (pin "46") (pinfunction "PB9_46") (pintype "passive+no_connect"))
    )
    (net (code "67") (name "unconnected-(U19-PB10-Pad21)") (class "Default")
      (node (ref "U19") (pin "21") (pinfunction "PB10_21") (pintype "passive+no_connect"))
    )
    (net (code "68") (name "unconnected-(U19-PB11-Pad22)") (class "Default")
      (node (ref "U19") (pin "22") (pinfunction "PB11_22") (pintype "passive+no_connect"))
    )
    (net (code "69") (name "unconnected-(U19-PC15-Pad4)") (class "Default")
      (node (ref "U19") (pin "4") (pinfunction "PC15_4") (pintype "passive+no_connect"))
    )
  )
)
